# EasyEDA_SCH-PicoPET_2021-11-24.net
KiCad netlist of a schematic drawn in EasyEDA
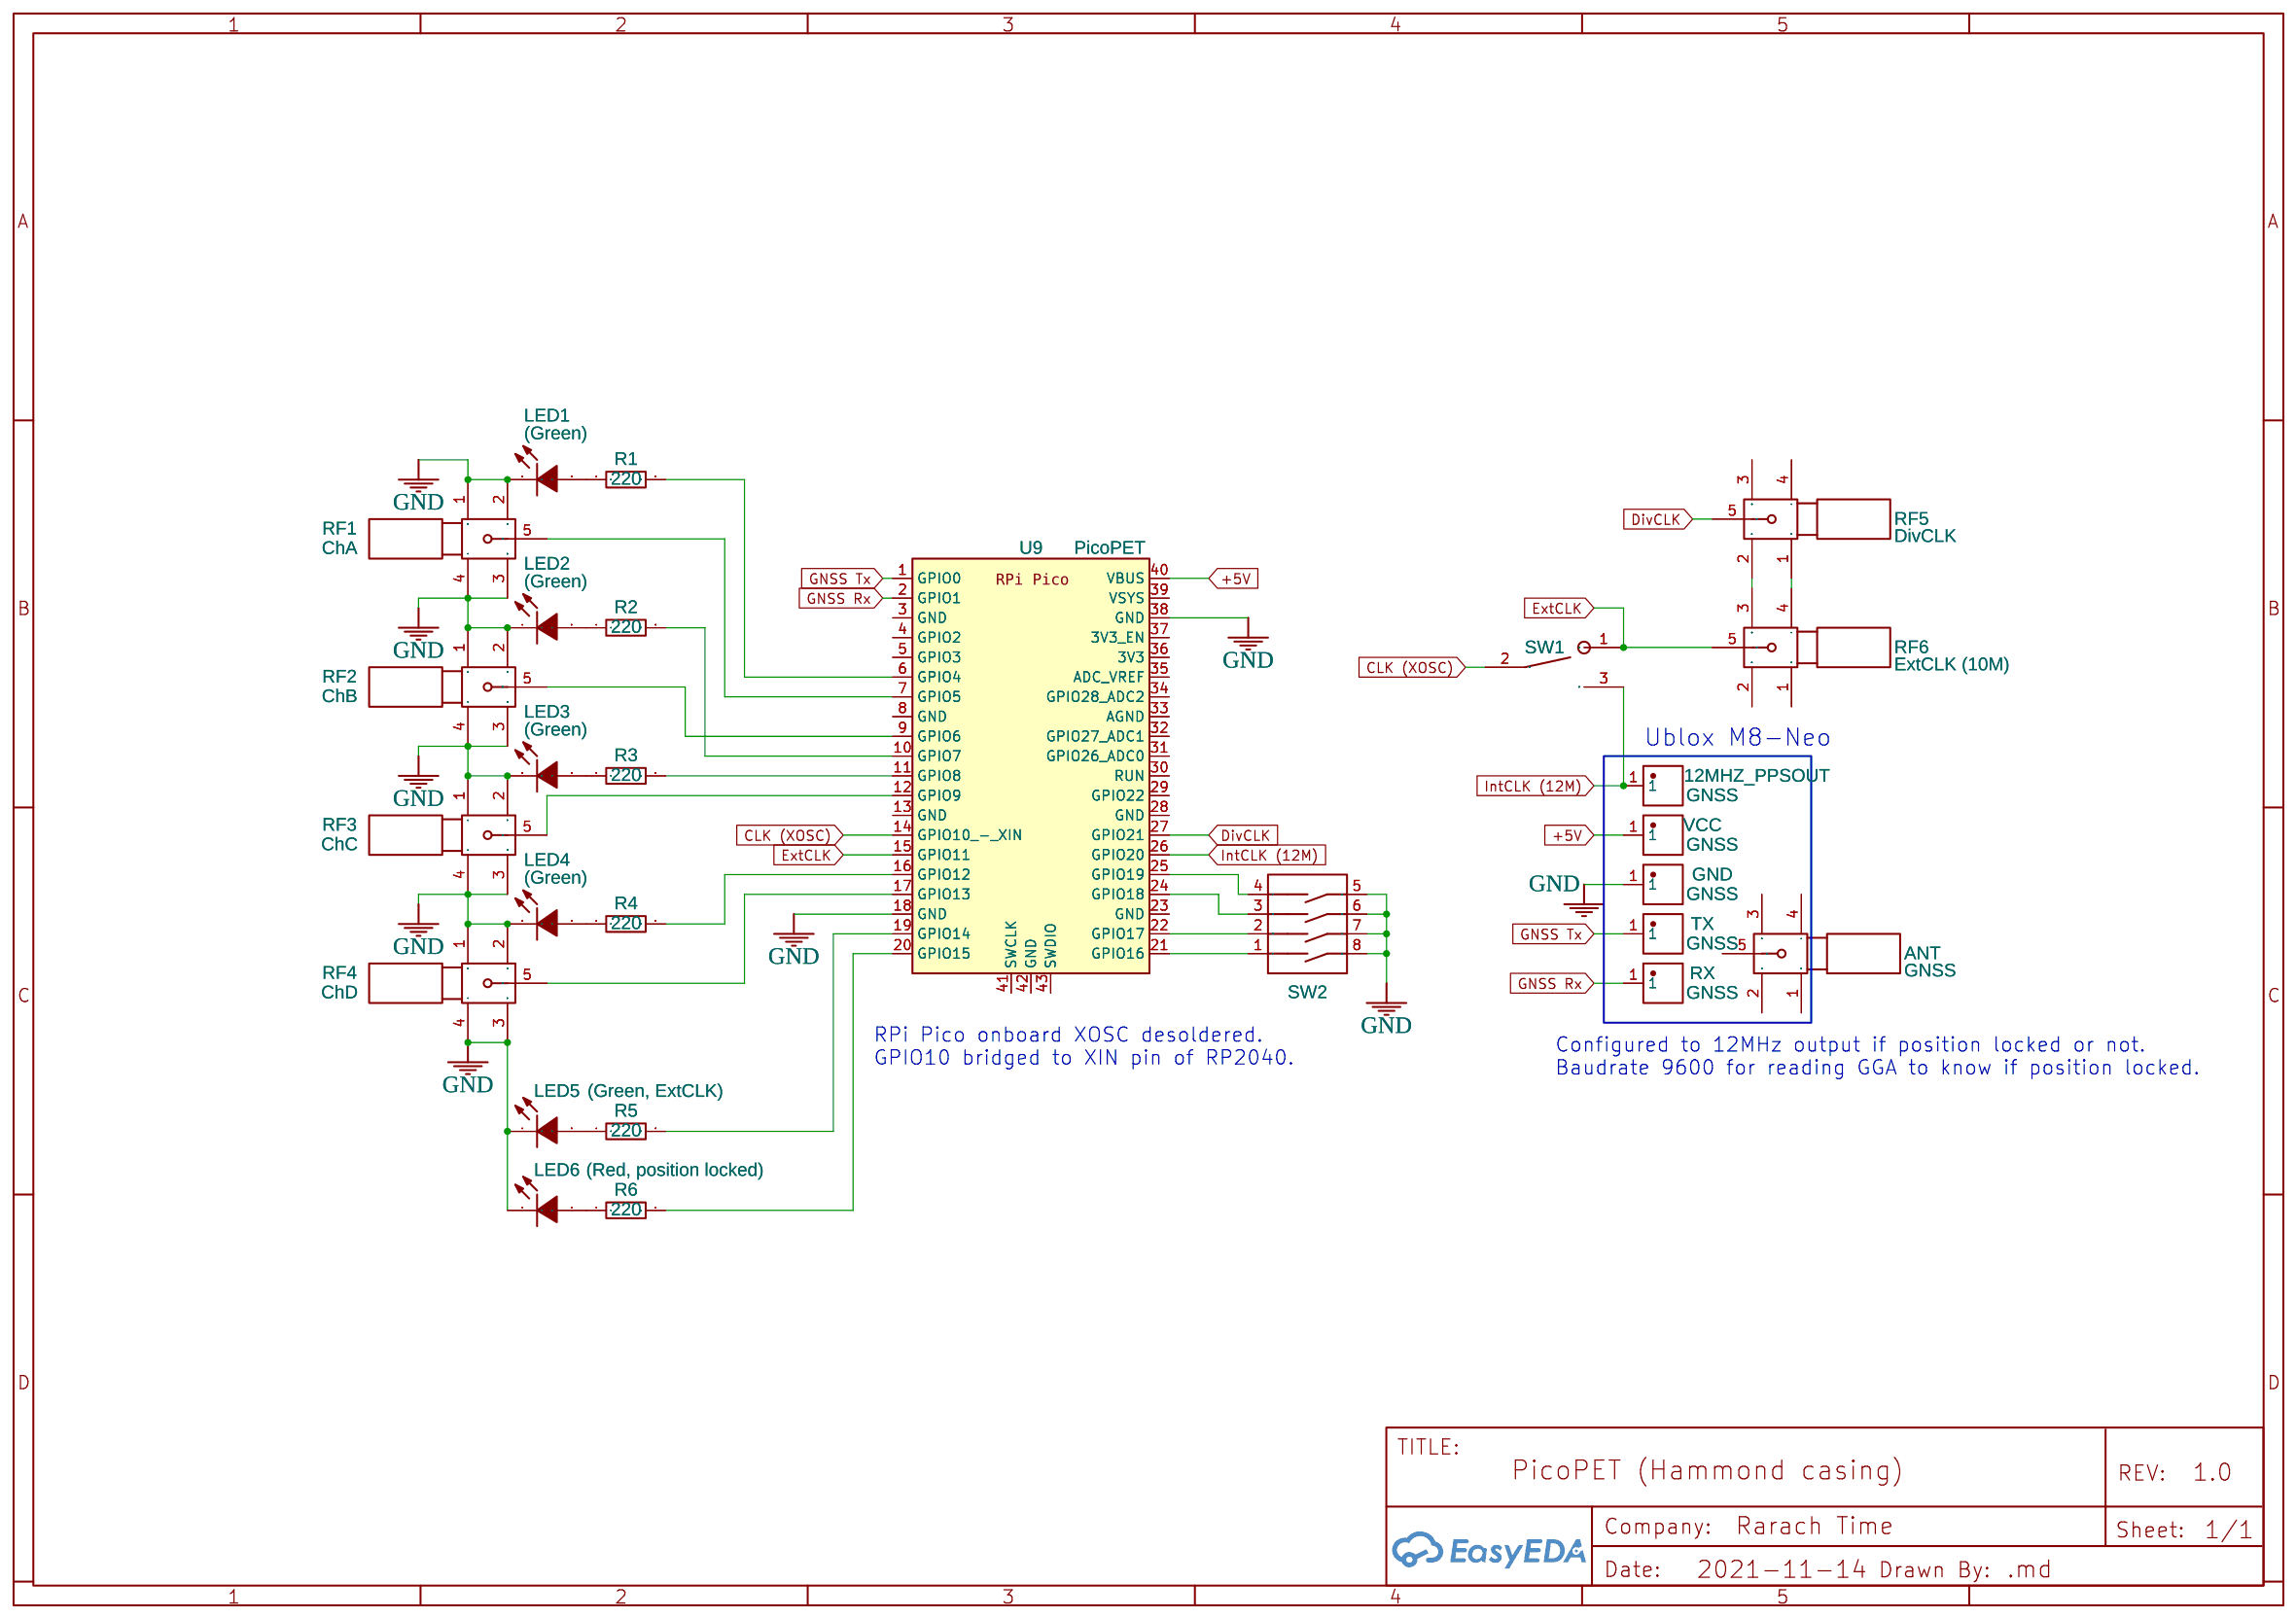
[diagram p0: schematic sheet]

(export (version "E")
  (design (tool "Eeschema 10.0.6"))
  (components
    (comp (ref "12MHZ_PPSOUT")
      (value "GNSS")
      (fields (field (name "BOM_Manufacturer Part") "RCSCTE") (field (name "BOM_Supplier Part") "C159866"))
      (libsource (lib "") (part "RCSCTE"))
    )
    (comp (ref "ANT")
      (value "GNSS")
      (fields
        (field (name "BOM_Manufacturer Part") "BWSMA-KE-P001")
        (field (name "BOM_Supplier Part") "C496550")
      )
      (libsource (lib "") (part "BWSMA-KE-P001_2"))
    )
    (comp (ref "GND")
      (value "GNSS")
      (fields (field (name "BOM_Manufacturer Part") "RCSCTE") (field (name "BOM_Supplier Part") "C159866"))
      (libsource (lib "") (part "RCSCTE_4"))
    )
    (comp (ref "LED1")
      (value "(Green)")
      (fields
        (field (name "BOM_Manufacturer Part") "0805G (Green)")
        (field (name "BOM_Supplier Part") "C2297")
      )
      (libsource (lib "") (part "0805G (Green)"))
    )
    (comp (ref "LED2")
      (value "(Green)")
      (fields
        (field (name "BOM_Manufacturer Part") "0805G (Green)")
        (field (name "BOM_Supplier Part") "C2297")
      )
      (libsource (lib "") (part "0805G (Green)"))
    )
    (comp (ref "LED3")
      (value "(Green)")
      (fields
        (field (name "BOM_Manufacturer Part") "0805G (Green)")
        (field (name "BOM_Supplier Part") "C2297")
      )
      (libsource (lib "") (part "0805G (Green)"))
    )
    (comp (ref "LED4")
      (value "(Green)")
      (fields
        (field (name "BOM_Manufacturer Part") "0805G (Green)")
        (field (name "BOM_Supplier Part") "C2297")
      )
      (libsource (lib "") (part "0805G (Green)"))
    )
    (comp (ref "LED5")
      (value "(Green, ExtCLK)")
      (fields
        (field (name "BOM_Manufacturer Part") "0805G (Green)")
        (field (name "BOM_Supplier Part") "C2297")
      )
      (libsource (lib "") (part "0805G (Green)"))
    )
    (comp (ref "LED6")
      (value "(Red, position locked)")
      (fields
        (field (name "BOM_Manufacturer Part") "0805G (Green)")
        (field (name "BOM_Supplier Part") "C2297")
      )
      (libsource (lib "") (part "0805G (Green)"))
    )
    (comp (ref "R1")
      (value "220")
      (fields
        (field (name "BOM_Manufacturer Part") "0805W8F2200T5E")
        (field (name "BOM_Supplier Part") "C17557")
      )
      (libsource (lib "") (part "0805W8F2200T5E"))
    )
    (comp (ref "R2")
      (value "220")
      (fields
        (field (name "BOM_Manufacturer Part") "0805W8F2200T5E")
        (field (name "BOM_Supplier Part") "C17557")
      )
      (libsource (lib "") (part "0805W8F2200T5E"))
    )
    (comp (ref "R3")
      (value "220")
      (fields
        (field (name "BOM_Manufacturer Part") "0805W8F2200T5E")
        (field (name "BOM_Supplier Part") "C17557")
      )
      (libsource (lib "") (part "0805W8F2200T5E"))
    )
    (comp (ref "R4")
      (value "220")
      (fields
        (field (name "BOM_Manufacturer Part") "0805W8F2200T5E")
        (field (name "BOM_Supplier Part") "C17557")
      )
      (libsource (lib "") (part "0805W8F2200T5E"))
    )
    (comp (ref "R5")
      (value "220")
      (fields
        (field (name "BOM_Manufacturer Part") "0805W8F2200T5E")
        (field (name "BOM_Supplier Part") "C17557")
      )
      (libsource (lib "") (part "0805W8F2200T5E"))
    )
    (comp (ref "R6")
      (value "220")
      (fields
        (field (name "BOM_Manufacturer Part") "0805W8F2200T5E")
        (field (name "BOM_Supplier Part") "C17557")
      )
      (libsource (lib "") (part "0805W8F2200T5E"))
    )
    (comp (ref "RF1")
      (value "ChA")
      (fields
        (field (name "BOM_Manufacturer Part") "BWSMA-KE-P001")
        (field (name "BOM_Supplier Part") "C496550")
      )
      (libsource (lib "") (part "BWSMA-KE-P001"))
    )
    (comp (ref "RF2")
      (value "ChB")
      (fields
        (field (name "BOM_Manufacturer Part") "BWSMA-KE-P001")
        (field (name "BOM_Supplier Part") "C496550")
      )
      (libsource (lib "") (part "BWSMA-KE-P001"))
    )
    (comp (ref "RF3")
      (value "ChC")
      (fields
        (field (name "BOM_Manufacturer Part") "BWSMA-KE-P001")
        (field (name "BOM_Supplier Part") "C496550")
      )
      (libsource (lib "") (part "BWSMA-KE-P001"))
    )
    (comp (ref "RF4")
      (value "ChD")
      (fields
        (field (name "BOM_Manufacturer Part") "BWSMA-KE-P001")
        (field (name "BOM_Supplier Part") "C496550")
      )
      (libsource (lib "") (part "BWSMA-KE-P001"))
    )
    (comp (ref "RF5")
      (value "DivCLK")
      (fields
        (field (name "BOM_Manufacturer Part") "BWSMA-KE-P001")
        (field (name "BOM_Supplier Part") "C496550")
      )
      (libsource (lib "") (part "BWSMA-KE-P001_1"))
    )
    (comp (ref "RF6")
      (value "ExtCLK (10M)")
      (fields
        (field (name "BOM_Manufacturer Part") "BWSMA-KE-P001")
        (field (name "BOM_Supplier Part") "C496550")
      )
      (libsource (lib "") (part "BWSMA-KE-P001_1"))
    )
    (comp (ref "RX")
      (value "GNSS")
      (fields (field (name "BOM_Manufacturer Part") "RCSCTE") (field (name "BOM_Supplier Part") "C159866"))
      (libsource (lib "") (part "RCSCTE_1"))
    )
    (comp (ref "SW1")
      (value "100SP4T1B4M2QE")
      (fields (field (name "BOM_Supplier Part") "C273358"))
      (libsource (lib "") (part "100SP4T1B4M2QE"))
    )
    (comp (ref "SW2")
      (value "HAD-04H-R")
      (fields
        (field (name "BOM_Manufacturer Part") "HAD-04H-R DIP switch")
        (field (name "BOM_Supplier Part") "C3693")
      )
      (libsource (lib "") (part "HAD-04H-R"))
    )
    (comp (ref "TX")
      (value "GNSS")
      (fields (field (name "BOM_Manufacturer Part") "RCSCTE") (field (name "BOM_Supplier Part") "C159866"))
      (libsource (lib "") (part "RCSCTE_3"))
    )
    (comp (ref "U9") (value "PicoPET") (libsource (lib "") (part "Pico")))
    (comp (ref "VCC")
      (value "GNSS")
      (fields (field (name "BOM_Manufacturer Part") "RCSCTE") (field (name "BOM_Supplier Part") "C159866"))
      (libsource (lib "") (part "RCSCTE_2"))
    )
  )
  (nets
    (net (code "1") (name "+5V") (class "Default")
      (node (ref "U9") (pin "40") (pinfunction "VBUS_40") (pintype "unspecified"))
      (node (ref "VCC") (pin "1") (pinfunction "1_1") (pintype "unspecified"))
    )
    (net (code "2") (name "CLK (XOSC)") (class "Default")
      (node (ref "SW1") (pin "2") (pinfunction "2_2") (pintype "input"))
      (node (ref "U9") (pin "14") (pinfunction "GPIO10_-_XIN_14") (pintype "bidirectional"))
    )
    (net (code "3") (name "DivCLK") (class "Default")
      (node (ref "RF5") (pin "5") (pinfunction "5_5") (pintype "unspecified"))
      (node (ref "U9") (pin "27") (pinfunction "GPIO21_27") (pintype "bidirectional"))
    )
    (net (code "4") (name "ExtCLK") (class "Default")
      (node (ref "RF6") (pin "5") (pinfunction "5_5") (pintype "unspecified"))
      (node (ref "SW1") (pin "1") (pinfunction "1_1") (pintype "input"))
      (node (ref "U9") (pin "15") (pinfunction "GPIO11_15") (pintype "bidirectional"))
    )
    (net (code "5") (name "GND") (class "Default")
      (node (ref "GND") (pin "1") (pinfunction "1_1") (pintype "unspecified"))
      (node (ref "LED1") (pin "1") (pinfunction "K_1") (pintype "unspecified"))
      (node (ref "LED2") (pin "1") (pinfunction "K_1") (pintype "unspecified"))
      (node (ref "LED3") (pin "1") (pinfunction "K_1") (pintype "unspecified"))
      (node (ref "LED4") (pin "1") (pinfunction "K_1") (pintype "unspecified"))
      (node (ref "LED5") (pin "1") (pinfunction "K_1") (pintype "unspecified"))
      (node (ref "LED6") (pin "1") (pinfunction "K_1") (pintype "unspecified"))
      (node (ref "RF1") (pin "1") (pinfunction "1_1") (pintype "unspecified"))
      (node (ref "RF1") (pin "2") (pinfunction "2_2") (pintype "unspecified"))
      (node (ref "RF1") (pin "3") (pinfunction "3_3") (pintype "unspecified"))
      (node (ref "RF1") (pin "4") (pinfunction "4_4") (pintype "unspecified"))
      (node (ref "RF2") (pin "1") (pinfunction "1_1") (pintype "unspecified"))
      (node (ref "RF2") (pin "2") (pinfunction "2_2") (pintype "unspecified"))
      (node (ref "RF2") (pin "3") (pinfunction "3_3") (pintype "unspecified"))
      (node (ref "RF2") (pin "4") (pinfunction "4_4") (pintype "unspecified"))
      (node (ref "RF3") (pin "1") (pinfunction "1_1") (pintype "unspecified"))
      (node (ref "RF3") (pin "2") (pinfunction "2_2") (pintype "unspecified"))
      (node (ref "RF3") (pin "3") (pinfunction "3_3") (pintype "unspecified"))
      (node (ref "RF3") (pin "4") (pinfunction "4_4") (pintype "unspecified"))
      (node (ref "RF4") (pin "1") (pinfunction "1_1") (pintype "unspecified"))
      (node (ref "RF4") (pin "2") (pinfunction "2_2") (pintype "unspecified"))
      (node (ref "RF4") (pin "3") (pinfunction "3_3") (pintype "unspecified"))
      (node (ref "RF4") (pin "4") (pinfunction "4_4") (pintype "unspecified"))
      (node (ref "SW2") (pin "5") (pinfunction "5_5") (pintype "unspecified"))
      (node (ref "SW2") (pin "6") (pinfunction "6_6") (pintype "unspecified"))
      (node (ref "SW2") (pin "7") (pinfunction "7_7") (pintype "unspecified"))
      (node (ref "SW2") (pin "8") (pinfunction "8_8") (pintype "unspecified"))
      (node (ref "U9") (pin "18") (pinfunction "GND_18") (pintype "bidirectional"))
      (node (ref "U9") (pin "38") (pinfunction "GND_38") (pintype "bidirectional"))
    )
    (net (code "6") (name "GNSS Rx") (class "Default")
      (node (ref "RX") (pin "1") (pinfunction "1_1") (pintype "unspecified"))
      (node (ref "U9") (pin "2") (pinfunction "GPIO1_2") (pintype "bidirectional"))
    )
    (net (code "7") (name "GNSS Tx") (class "Default")
      (node (ref "TX") (pin "1") (pinfunction "1_1") (pintype "unspecified"))
      (node (ref "U9") (pin "1") (pinfunction "GPIO0_1") (pintype "bidirectional"))
    )
    (net (code "8") (name "IntCLK (12M)") (class "Default")
      (node (ref "12MHZ_PPSOUT") (pin "1") (pinfunction "1_1") (pintype "unspecified"))
      (node (ref "SW1") (pin "3") (pinfunction "3_3") (pintype "input"))
      (node (ref "U9") (pin "26") (pinfunction "GPIO20_26") (pintype "bidirectional"))
    )
    (net (code "9") (name "Net-(LED1-A)") (class "Default")
      (node (ref "LED1") (pin "2") (pinfunction "A_2") (pintype "unspecified"))
      (node (ref "R1") (pin "1") (pinfunction "1_1") (pintype "input"))
    )
    (net (code "10") (name "Net-(LED2-A)") (class "Default")
      (node (ref "LED2") (pin "2") (pinfunction "A_2") (pintype "unspecified"))
      (node (ref "R2") (pin "1") (pinfunction "1_1") (pintype "input"))
    )
    (net (code "11") (name "Net-(LED3-A)") (class "Default")
      (node (ref "LED3") (pin "2") (pinfunction "A_2") (pintype "unspecified"))
      (node (ref "R3") (pin "1") (pinfunction "1_1") (pintype "input"))
    )
    (net (code "12") (name "Net-(LED4-A)") (class "Default")
      (node (ref "LED4") (pin "2") (pinfunction "A_2") (pintype "unspecified"))
      (node (ref "R4") (pin "1") (pinfunction "1_1") (pintype "input"))
    )
    (net (code "13") (name "Net-(LED5-A)") (class "Default")
      (node (ref "LED5") (pin "2") (pinfunction "A_2") (pintype "unspecified"))
      (node (ref "R5") (pin "1") (pinfunction "1_1") (pintype "input"))
    )
    (net (code "14") (name "Net-(LED6-A)") (class "Default")
      (node (ref "LED6") (pin "2") (pinfunction "A_2") (pintype "unspecified"))
      (node (ref "R6") (pin "1") (pinfunction "1_1") (pintype "input"))
    )
    (net (code "15") (name "Net-(RF5-Pad1)") (class "Default")
      (node (ref "RF5") (pin "1") (pinfunction "1_1") (pintype "unspecified"))
      (node (ref "RF6") (pin "4") (pinfunction "4_4") (pintype "unspecified"))
    )
    (net (code "16") (name "Net-(RF5-Pad2)") (class "Default")
      (node (ref "RF5") (pin "2") (pinfunction "2_2") (pintype "unspecified"))
      (node (ref "RF6") (pin "3") (pinfunction "3_3") (pintype "unspecified"))
    )
    (net (code "17") (name "Net-(U9-GPIO4)") (class "Default")
      (node (ref "R1") (pin "2") (pinfunction "2_2") (pintype "input"))
      (node (ref "U9") (pin "6") (pinfunction "GPIO4_6") (pintype "bidirectional"))
    )
    (net (code "18") (name "Net-(U9-GPIO5)") (class "Default")
      (node (ref "RF1") (pin "5") (pinfunction "5_5") (pintype "unspecified"))
      (node (ref "U9") (pin "7") (pinfunction "GPIO5_7") (pintype "bidirectional"))
    )
    (net (code "19") (name "Net-(U9-GPIO6)") (class "Default")
      (node (ref "RF2") (pin "5") (pinfunction "5_5") (pintype "unspecified"))
      (node (ref "U9") (pin "9") (pinfunction "GPIO6_9") (pintype "bidirectional"))
    )
    (net (code "20") (name "Net-(U9-GPIO7)") (class "Default")
      (node (ref "R2") (pin "2") (pinfunction "2_2") (pintype "input"))
      (node (ref "U9") (pin "10") (pinfunction "GPIO7_10") (pintype "bidirectional"))
    )
    (net (code "21") (name "Net-(U9-GPIO8)") (class "Default")
      (node (ref "R3") (pin "2") (pinfunction "2_2") (pintype "input"))
      (node (ref "U9") (pin "11") (pinfunction "GPIO8_11") (pintype "bidirectional"))
    )
    (net (code "22") (name "Net-(U9-GPIO9)") (class "Default")
      (node (ref "RF3") (pin "5") (pinfunction "5_5") (pintype "unspecified"))
      (node (ref "U9") (pin "12") (pinfunction "GPIO9_12") (pintype "bidirectional"))
    )
    (net (code "23") (name "Net-(U9-GPIO12)") (class "Default")
      (node (ref "R4") (pin "2") (pinfunction "2_2") (pintype "input"))
      (node (ref "U9") (pin "16") (pinfunction "GPIO12_16") (pintype "bidirectional"))
    )
    (net (code "24") (name "Net-(U9-GPIO13)") (class "Default")
      (node (ref "RF4") (pin "5") (pinfunction "5_5") (pintype "unspecified"))
      (node (ref "U9") (pin "17") (pinfunction "GPIO13_17") (pintype "bidirectional"))
    )
    (net (code "25") (name "Net-(U9-GPIO14)") (class "Default")
      (node (ref "R5") (pin "2") (pinfunction "2_2") (pintype "input"))
      (node (ref "U9") (pin "19") (pinfunction "GPIO14_19") (pintype "bidirectional"))
    )
    (net (code "26") (name "Net-(U9-GPIO15)") (class "Default")
      (node (ref "R6") (pin "2") (pinfunction "2_2") (pintype "input"))
      (node (ref "U9") (pin "20") (pinfunction "GPIO15_20") (pintype "bidirectional"))
    )
    (net (code "27") (name "Net-(U9-GPIO16)") (class "Default")
      (node (ref "SW2") (pin "1") (pinfunction "1_1") (pintype "unspecified"))
      (node (ref "U9") (pin "21") (pinfunction "GPIO16_21") (pintype "bidirectional"))
    )
    (net (code "28") (name "Net-(U9-GPIO17)") (class "Default")
      (node (ref "SW2") (pin "2") (pinfunction "2_2") (pintype "unspecified"))
      (node (ref "U9") (pin "22") (pinfunction "GPIO17_22") (pintype "bidirectional"))
    )
    (net (code "29") (name "Net-(U9-GPIO18)") (class "Default")
      (node (ref "SW2") (pin "3") (pinfunction "3_3") (pintype "unspecified"))
      (node (ref "U9") (pin "24") (pinfunction "GPIO18_24") (pintype "bidirectional"))
    )
    (net (code "30") (name "Net-(U9-GPIO19)") (class "Default")
      (node (ref "SW2") (pin "4") (pinfunction "4_4") (pintype "unspecified"))
      (node (ref "U9") (pin "25") (pinfunction "GPIO19_25") (pintype "bidirectional"))
    )
    (net (code "31") (name "unconnected-(ANT-Pad1)") (class "Default")
      (node (ref "ANT") (pin "1") (pinfunction "1_1") (pintype "unspecified"))
    )
    (net (code "32") (name "unconnected-(ANT-Pad2)") (class "Default")
      (node (ref "ANT") (pin "2") (pinfunction "2_2") (pintype "unspecified"))
    )
    (net (code "33") (name "unconnected-(ANT-Pad3)") (class "Default")
      (node (ref "ANT") (pin "3") (pinfunction "3_3") (pintype "unspecified"))
    )
    (net (code "34") (name "unconnected-(ANT-Pad4)") (class "Default")
      (node (ref "ANT") (pin "4") (pinfunction "4_4") (pintype "unspecified"))
    )
    (net (code "35") (name "unconnected-(ANT-Pad5)") (class "Default")
      (node (ref "ANT") (pin "5") (pinfunction "5_5") (pintype "unspecified"))
    )
    (net (code "36") (name "unconnected-(RF5-Pad3)") (class "Default")
      (node (ref "RF5") (pin "3") (pinfunction "3_3") (pintype "unspecified"))
    )
    (net (code "37") (name "unconnected-(RF5-Pad4)") (class "Default")
      (node (ref "RF5") (pin "4") (pinfunction "4_4") (pintype "unspecified"))
    )
    (net (code "38") (name "unconnected-(RF6-Pad1)") (class "Default")
      (node (ref "RF6") (pin "1") (pinfunction "1_1") (pintype "unspecified"))
    )
    (net (code "39") (name "unconnected-(RF6-Pad2)") (class "Default")
      (node (ref "RF6") (pin "2") (pinfunction "2_2") (pintype "unspecified"))
    )
    (net (code "40") (name "unconnected-(U9-3V3-Pad36)") (class "Default")
      (node (ref "U9") (pin "36") (pinfunction "3V3_36") (pintype "unspecified"))
    )
    (net (code "41") (name "unconnected-(U9-3V3_EN-Pad37)") (class "Default")
      (node (ref "U9") (pin "37") (pinfunction "3V3_EN_37") (pintype "input"))
    )
    (net (code "42") (name "unconnected-(U9-ADC_VREF-Pad35)") (class "Default")
      (node (ref "U9") (pin "35") (pinfunction "ADC_VREF_35") (pintype "unspecified"))
    )
    (net (code "43") (name "unconnected-(U9-AGND-Pad33)") (class "Default")
      (node (ref "U9") (pin "33") (pinfunction "AGND_33") (pintype "bidirectional"))
    )
    (net (code "44") (name "unconnected-(U9-GND-Pad3)") (class "Default")
      (node (ref "U9") (pin "3") (pinfunction "GND_3") (pintype "bidirectional"))
    )
    (net (code "45") (name "unconnected-(U9-GND-Pad8)") (class "Default")
      (node (ref "U9") (pin "8") (pinfunction "GND_8") (pintype "bidirectional"))
    )
    (net (code "46") (name "unconnected-(U9-GND-Pad13)") (class "Default")
      (node (ref "U9") (pin "13") (pinfunction "GND_13") (pintype "bidirectional"))
    )
    (net (code "47") (name "unconnected-(U9-GND-Pad23)") (class "Default")
      (node (ref "U9") (pin "23") (pinfunction "GND_23") (pintype "bidirectional"))
    )
    (net (code "48") (name "unconnected-(U9-GND-Pad28)") (class "Default")
      (node (ref "U9") (pin "28") (pinfunction "GND_28") (pintype "bidirectional"))
    )
    (net (code "49") (name "unconnected-(U9-GND-Pad42)") (class "Default")
      (node (ref "U9") (pin "42") (pinfunction "GND_42") (pintype "bidirectional"))
    )
    (net (code "50") (name "unconnected-(U9-GPIO2-Pad4)") (class "Default")
      (node (ref "U9") (pin "4") (pinfunction "GPIO2_4") (pintype "bidirectional"))
    )
    (net (code "51") (name "unconnected-(U9-GPIO3-Pad5)") (class "Default")
      (node (ref "U9") (pin "5") (pinfunction "GPIO3_5") (pintype "bidirectional"))
    )
    (net (code "52") (name "unconnected-(U9-GPIO22-Pad29)") (class "Default")
      (node (ref "U9") (pin "29") (pinfunction "GPIO22_29") (pintype "bidirectional"))
    )
    (net (code "53") (name "unconnected-(U9-GPIO26_ADC0-Pad31)") (class "Default")
      (node (ref "U9") (pin "31") (pinfunction "GPIO26_ADC0_31") (pintype "bidirectional"))
    )
    (net (code "54") (name "unconnected-(U9-GPIO27_ADC1-Pad32)") (class "Default")
      (node (ref "U9") (pin "32") (pinfunction "GPIO27_ADC1_32") (pintype "bidirectional"))
    )
    (net (code "55") (name "unconnected-(U9-GPIO28_ADC2-Pad34)") (class "Default")
      (node (ref "U9") (pin "34") (pinfunction "GPIO28_ADC2_34") (pintype "bidirectional"))
    )
    (net (code "56") (name "unconnected-(U9-RUN-Pad30)") (class "Default")
      (node (ref "U9") (pin "30") (pinfunction "RUN_30") (pintype "input"))
    )
    (net (code "57") (name "unconnected-(U9-SWCLK-Pad41)") (class "Default")
      (node (ref "U9") (pin "41") (pinfunction "SWCLK_41") (pintype "input"))
    )
    (net (code "58") (name "unconnected-(U9-SWDIO-Pad43)") (class "Default")
      (node (ref "U9") (pin "43") (pinfunction "SWDIO_43") (pintype "bidirectional"))
    )
    (net (code "59") (name "unconnected-(U9-VSYS-Pad39)") (class "Default")
      (node (ref "U9") (pin "39") (pinfunction "VSYS_39") (pintype "unspecified"))
    )
  )
)
